# gambaran_rev1.net
KiCad netlist of a schematic drawn in EAGLE
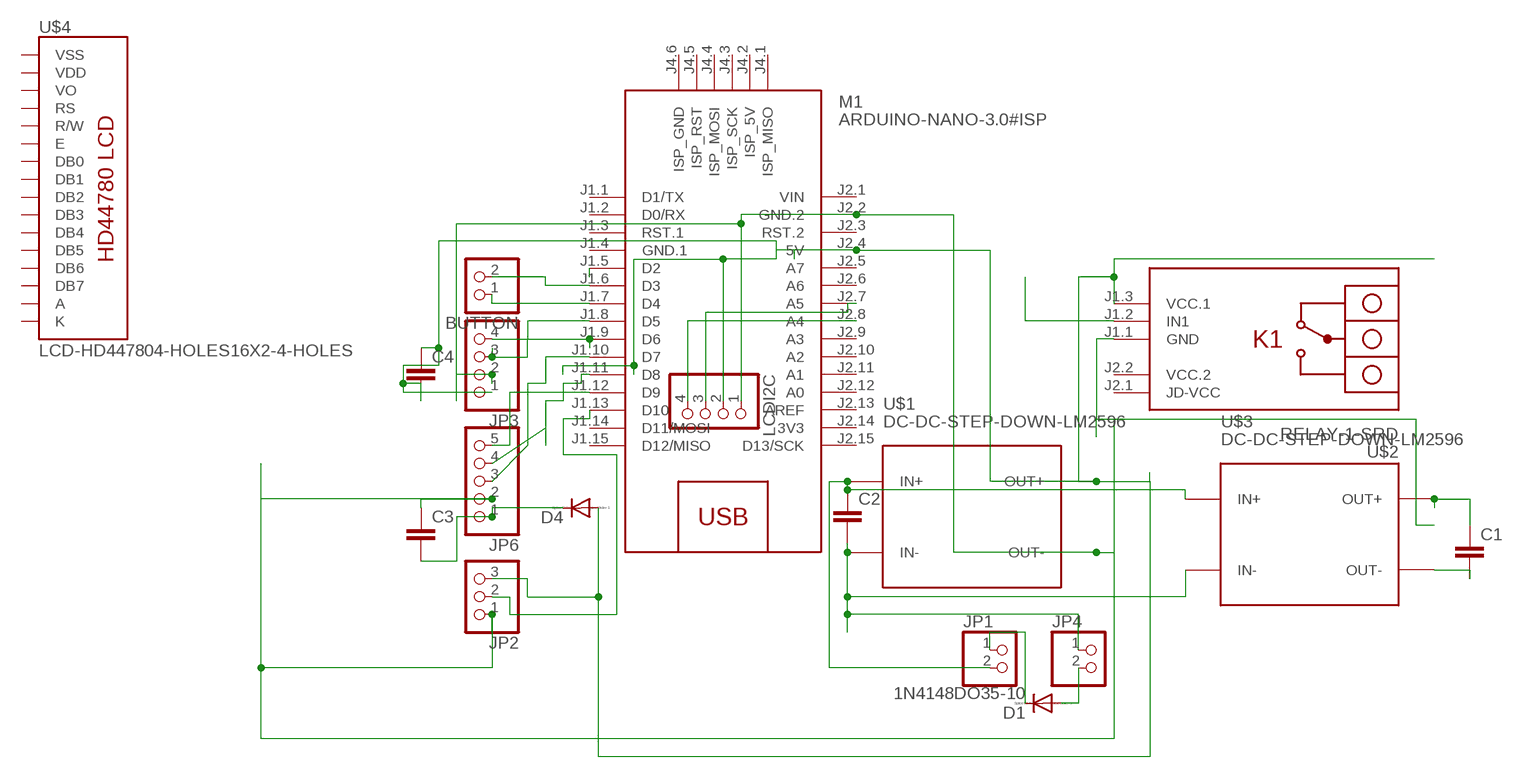
[diagram p0: schematic, sheet 1]

(export (version "E")
  (design (tool "Eeschema 10.0.6"))
  (components
    (comp (ref "BUTTON")
      (value "PINHD-1X2/90")
      (footprint "eagle-import:1X02_90")
      (libsource (lib "eagle-import") (part "PINHD-1X2/90"))
    )
    (comp (ref "C1")
      (value "C2.5/6")
      (footprint "eagle-import:C2.5-6")
      (libsource (lib "eagle-import") (part "C2.5/6"))
    )
    (comp (ref "C2")
      (value "C2.5/6")
      (footprint "eagle-import:C2.5-6")
      (libsource (lib "eagle-import") (part "C2.5/6"))
    )
    (comp (ref "C3")
      (value "C2.5/6")
      (footprint "eagle-import:C2.5-6")
      (libsource (lib "eagle-import") (part "C2.5/6"))
    )
    (comp (ref "C4")
      (value "C2.5/6")
      (footprint "eagle-import:C2.5-6")
      (libsource (lib "eagle-import") (part "C2.5/6"))
    )
    (comp (ref "D1")
      (value "1N4148DO35-10")
      (footprint "eagle-import:DO35-10")
      (libsource (lib "eagle-import") (part "1N4148DO35-10"))
    )
    (comp (ref "D4")
      (value "1N4148DO35-10")
      (footprint "eagle-import:DO35-10")
      (libsource (lib "eagle-import") (part "1N4148DO35-10"))
    )
    (comp (ref "JP1")
      (value "PINHD-1X2/90")
      (footprint "eagle-import:1X02_90")
      (libsource (lib "eagle-import") (part "PINHD-1X2/90"))
    )
    (comp (ref "JP2")
      (value "PINHD-1X3")
      (footprint "eagle-import:1X03")
      (libsource (lib "eagle-import") (part "PINHD-1X3"))
    )
    (comp (ref "JP3")
      (value "PINHD-1X4/90")
      (footprint "eagle-import:1X04_90")
      (libsource (lib "eagle-import") (part "PINHD-1X4/90"))
    )
    (comp (ref "JP4")
      (value "PINHD-1X2/90")
      (footprint "eagle-import:1X02_90")
      (libsource (lib "eagle-import") (part "PINHD-1X2/90"))
    )
    (comp (ref "JP6")
      (value "PINHD-1X5")
      (footprint "eagle-import:1X05")
      (libsource (lib "eagle-import") (part "PINHD-1X5"))
    )
    (comp (ref "LCDI2C")
      (value "PINHD-1X4/90")
      (footprint "eagle-import:1X04_90")
      (libsource (lib "eagle-import") (part "PINHD-1X4/90"))
    )
    (comp (ref "M1")
      (value "ARDUINO-NANO-3.0#ISP")
      (footprint "eagle-import:ARDUINO-NANO-3.0#ISP")
      (libsource (lib "eagle-import") (part "ARDUINO-NANO-3.0#ISP"))
    )
    (comp (ref "U$1")
      (value "DC-DC-STEP-DOWN-LM2596")
      (footprint "eagle-import:DC-DC-STEP-DOWN-LM2596")
      (libsource (lib "eagle-import") (part "DC-DC-STEP-DOWN-LM2596"))
    )
    (comp (ref "U$2")
      (value "RELAY-1-SRD")
      (footprint "eagle-import:RELAY-1-SRD")
      (libsource (lib "eagle-import") (part "RELAY-1-SRD"))
    )
    (comp (ref "U$3")
      (value "DC-DC-STEP-DOWN-LM2596")
      (footprint "eagle-import:DC-DC-STEP-DOWN-LM2596")
      (libsource (lib "eagle-import") (part "DC-DC-STEP-DOWN-LM2596"))
    )
    (comp (ref "U$4")
      (value "LCD-HD447804-HOLES16X2-4-HOLES")
      (footprint "eagle-import:LCD-16X2-4HOLES")
      (libsource (lib "eagle-import") (part "LCD-HD4478016X2-4-HOLES4-HOLES"))
    )
  )
  (nets
    (net (code "1") (name "/3V3") (class "Default")
      (node (ref "M1") (pin "J2.14") (pinfunction "3V3_J2.14") (pintype "power_in"))
    )
    (net (code "2") (name "/A") (class "Default")
      (node (ref "U$4") (pin "15") (pinfunction "A_15") (pintype "power_in"))
    )
    (net (code "3") (name "/GND.1") (class "Default")
      (node (ref "M1") (pin "J1.4") (pinfunction "GND.1_J1.4") (pintype "power_in"))
    )
    (net (code "4") (name "/K") (class "Default")
      (node (ref "U$4") (pin "16") (pinfunction "K_16") (pintype "power_in"))
    )
    (net (code "5") (name "/VCC.2") (class "Default")
      (node (ref "U$2") (pin "J2.2") (pinfunction "VCC.2_J2.2") (pintype "power_in"))
    )
    (net (code "6") (name "/VDD") (class "Default")
      (node (ref "U$4") (pin "2") (pinfunction "VDD_2") (pintype "power_in"))
    )
    (net (code "7") (name "/VIN") (class "Default")
      (node (ref "M1") (pin "J2.1") (pinfunction "VIN_J2.1") (pintype "power_in"))
    )
    (net (code "8") (name "/VSS") (class "Default")
      (node (ref "U$4") (pin "1") (pinfunction "VSS_1") (pintype "power_in"))
    )
    (net (code "9") (name "Net-(C1-Pad1)") (class "Default")
      (node (ref "C1") (pin "1") (pinfunction "1_1") (pintype "passive"))
      (node (ref "U$3") (pin "OUT+") (pinfunction "OUT+_OUT+") (pintype "bidirectional"))
    )
    (net (code "10") (name "Net-(C1-Pad2)") (class "Default")
      (node (ref "C1") (pin "2") (pinfunction "2_2") (pintype "passive"))
      (node (ref "U$3") (pin "OUT-") (pinfunction "OUT-_OUT-") (pintype "bidirectional"))
    )
    (net (code "11") (name "Net-(C2-Pad1)") (class "Default")
      (node (ref "C2") (pin "1") (pinfunction "1_1") (pintype "passive"))
      (node (ref "JP1") (pin "2") (pinfunction "2_2") (pintype "passive"))
      (node (ref "U$1") (pin "IN+") (pinfunction "IN+_IN+") (pintype "bidirectional"))
      (node (ref "U$3") (pin "IN+") (pinfunction "IN+_IN+") (pintype "bidirectional"))
    )
    (net (code "12") (name "Net-(C2-Pad2)") (class "Default")
      (node (ref "C2") (pin "2") (pinfunction "2_2") (pintype "passive"))
      (node (ref "JP4") (pin "1") (pinfunction "1_1") (pintype "passive"))
      (node (ref "U$1") (pin "IN-") (pinfunction "IN-_IN-") (pintype "bidirectional"))
      (node (ref "U$3") (pin "IN-") (pinfunction "IN-_IN-") (pintype "bidirectional"))
    )
    (net (code "13") (name "Net-(C3-Pad2)") (class "Default")
      (node (ref "C3") (pin "2") (pinfunction "2_2") (pintype "passive"))
      (node (ref "D4") (pin "C") (pinfunction "C_C") (pintype "passive"))
      (node (ref "JP6") (pin "1") (pinfunction "1_1") (pintype "passive"))
    )
    (net (code "14") (name "Net-(D1-PadA)") (class "Default")
      (node (ref "D1") (pin "A") (pinfunction "A_A") (pintype "passive"))
      (node (ref "JP4") (pin "2") (pinfunction "2_2") (pintype "passive"))
    )
    (net (code "15") (name "Net-(D1-PadC)") (class "Default")
      (node (ref "D1") (pin "C") (pinfunction "C_C") (pintype "passive"))
      (node (ref "JP1") (pin "1") (pinfunction "1_1") (pintype "passive"))
    )
    (net (code "16") (name "Net-(M1-5V)") (class "Default")
      (node (ref "C4") (pin "1") (pinfunction "1_1") (pintype "passive"))
      (node (ref "C4") (pin "2") (pinfunction "2_2") (pintype "passive"))
      (node (ref "D4") (pin "A") (pinfunction "A_A") (pintype "passive"))
      (node (ref "JP2") (pin "3") (pinfunction "3_3") (pintype "passive"))
      (node (ref "JP3") (pin "1") (pinfunction "1_1") (pintype "passive"))
      (node (ref "LCDI2C") (pin "2") (pinfunction "2_2") (pintype "passive"))
      (node (ref "M1") (pin "J2.4") (pinfunction "5V_J2.4") (pintype "power_in"))
      (node (ref "U$1") (pin "OUT+") (pinfunction "OUT+_OUT+") (pintype "bidirectional"))
      (node (ref "U$2") (pin "J1.3") (pinfunction "VCC.1_J1.3") (pintype "power_in"))
    )
    (net (code "17") (name "Net-(M1-A4)") (class "Default")
      (node (ref "LCDI2C") (pin "4") (pinfunction "4_4") (pintype "passive"))
      (node (ref "M1") (pin "J2.8") (pinfunction "A4_J2.8") (pintype "bidirectional"))
    )
    (net (code "18") (name "Net-(M1-A5)") (class "Default")
      (node (ref "LCDI2C") (pin "3") (pinfunction "3_3") (pintype "passive"))
      (node (ref "M1") (pin "J2.7") (pinfunction "A5_J2.7") (pintype "bidirectional"))
    )
    (net (code "19") (name "Net-(M1-D3)") (class "Default")
      (node (ref "BUTTON") (pin "2") (pinfunction "2_2") (pintype "passive"))
      (node (ref "M1") (pin "J1.6") (pinfunction "D3_J1.6") (pintype "bidirectional"))
    )
    (net (code "20") (name "Net-(M1-D4)") (class "Default")
      (node (ref "BUTTON") (pin "1") (pinfunction "1_1") (pintype "passive"))
      (node (ref "M1") (pin "J1.7") (pinfunction "D4_J1.7") (pintype "bidirectional"))
    )
    (net (code "21") (name "Net-(M1-D5)") (class "Default")
      (node (ref "JP3") (pin "3") (pinfunction "3_3") (pintype "passive"))
      (node (ref "M1") (pin "J1.8") (pinfunction "D5_J1.8") (pintype "bidirectional"))
    )
    (net (code "22") (name "Net-(M1-D6)") (class "Default")
      (node (ref "JP3") (pin "4") (pinfunction "4_4") (pintype "passive"))
      (node (ref "M1") (pin "J1.9") (pinfunction "D6_J1.9") (pintype "bidirectional"))
    )
    (net (code "23") (name "Net-(M1-D7)") (class "Default")
      (node (ref "JP6") (pin "3") (pinfunction "3_3") (pintype "passive"))
      (node (ref "M1") (pin "J1.10") (pinfunction "D7_J1.10") (pintype "bidirectional"))
    )
    (net (code "24") (name "Net-(M1-D8)") (class "Default")
      (node (ref "JP6") (pin "4") (pinfunction "4_4") (pintype "passive"))
      (node (ref "M1") (pin "J1.11") (pinfunction "D8_J1.11") (pintype "bidirectional"))
    )
    (net (code "25") (name "Net-(M1-D9)") (class "Default")
      (node (ref "JP6") (pin "5") (pinfunction "5_5") (pintype "passive"))
      (node (ref "M1") (pin "J1.12") (pinfunction "D9_J1.12") (pintype "bidirectional"))
    )
    (net (code "26") (name "Net-(M1-D10)") (class "Default")
      (node (ref "JP2") (pin "2") (pinfunction "2_2") (pintype "passive"))
      (node (ref "M1") (pin "J1.13") (pinfunction "D10_J1.13") (pintype "bidirectional"))
    )
    (net (code "27") (name "Net-(M1-GND.2)") (class "Default")
      (node (ref "C3") (pin "1") (pinfunction "1_1") (pintype "passive"))
      (node (ref "JP2") (pin "1") (pinfunction "1_1") (pintype "passive"))
      (node (ref "JP3") (pin "2") (pinfunction "2_2") (pintype "passive"))
      (node (ref "JP6") (pin "2") (pinfunction "2_2") (pintype "passive"))
      (node (ref "LCDI2C") (pin "1") (pinfunction "1_1") (pintype "passive"))
      (node (ref "M1") (pin "J2.2") (pinfunction "GND.2_J2.2") (pintype "power_in"))
      (node (ref "U$1") (pin "OUT-") (pinfunction "OUT-_OUT-") (pintype "bidirectional"))
      (node (ref "U$2") (pin "J1.1") (pinfunction "GND_J1.1") (pintype "power_in"))
    )
    (net (code "28") (name "unconnected-(M1-A0-PadJ2.12)") (class "Default")
      (node (ref "M1") (pin "J2.12") (pinfunction "A0_J2.12") (pintype "bidirectional"))
    )
    (net (code "29") (name "unconnected-(M1-A1-PadJ2.11)") (class "Default")
      (node (ref "M1") (pin "J2.11") (pinfunction "A1_J2.11") (pintype "bidirectional"))
    )
    (net (code "30") (name "unconnected-(M1-A2-PadJ2.10)") (class "Default")
      (node (ref "M1") (pin "J2.10") (pinfunction "A2_J2.10") (pintype "bidirectional"))
    )
    (net (code "31") (name "unconnected-(M1-A3-PadJ2.9)") (class "Default")
      (node (ref "M1") (pin "J2.9") (pinfunction "A3_J2.9") (pintype "bidirectional"))
    )
    (net (code "32") (name "unconnected-(M1-A6-PadJ2.6)") (class "Default")
      (node (ref "M1") (pin "J2.6") (pinfunction "A6_J2.6") (pintype "bidirectional"))
    )
    (net (code "33") (name "unconnected-(M1-A7-PadJ2.5)") (class "Default")
      (node (ref "M1") (pin "J2.5") (pinfunction "A7_J2.5") (pintype "bidirectional"))
    )
    (net (code "34") (name "unconnected-(M1-AREF-PadJ2.13)") (class "Default")
      (node (ref "M1") (pin "J2.13") (pinfunction "AREF_J2.13") (pintype "bidirectional"))
    )
    (net (code "35") (name "unconnected-(M1-D0{slash}RX-PadJ1.2)") (class "Default")
      (node (ref "M1") (pin "J1.2") (pinfunction "D0/RX_J1.2") (pintype "bidirectional"))
    )
    (net (code "36") (name "unconnected-(M1-D1{slash}TX-PadJ1.1)") (class "Default")
      (node (ref "M1") (pin "J1.1") (pinfunction "D1/TX_J1.1") (pintype "bidirectional"))
    )
    (net (code "37") (name "unconnected-(M1-D2-PadJ1.5)") (class "Default")
      (node (ref "M1") (pin "J1.5") (pinfunction "D2_J1.5") (pintype "bidirectional"))
    )
    (net (code "38") (name "unconnected-(M1-D11{slash}MOSI-PadJ1.14)") (class "Default")
      (node (ref "M1") (pin "J1.14") (pinfunction "D11/MOSI_J1.14") (pintype "bidirectional"))
    )
    (net (code "39") (name "unconnected-(M1-D12{slash}MISO-PadJ1.15)") (class "Default")
      (node (ref "M1") (pin "J1.15") (pinfunction "D12/MISO_J1.15") (pintype "bidirectional"))
    )
    (net (code "40") (name "unconnected-(M1-D13{slash}SCK-PadJ2.15)") (class "Default")
      (node (ref "M1") (pin "J2.15") (pinfunction "D13/SCK_J2.15") (pintype "bidirectional"))
    )
    (net (code "41") (name "unconnected-(M1-ISP_5V-PadJ4.2)") (class "Default")
      (node (ref "M1") (pin "J4.2") (pinfunction "ISP_5V_J4.2") (pintype "bidirectional"))
    )
    (net (code "42") (name "unconnected-(M1-ISP_GND-PadJ4.6)") (class "Default")
      (node (ref "M1") (pin "J4.6") (pinfunction "ISP_GND_J4.6") (pintype "bidirectional"))
    )
    (net (code "43") (name "unconnected-(M1-ISP_MISO-PadJ4.1)") (class "Default")
      (node (ref "M1") (pin "J4.1") (pinfunction "ISP_MISO_J4.1") (pintype "bidirectional"))
    )
    (net (code "44") (name "unconnected-(M1-ISP_MOSI-PadJ4.4)") (class "Default")
      (node (ref "M1") (pin "J4.4") (pinfunction "ISP_MOSI_J4.4") (pintype "bidirectional"))
    )
    (net (code "45") (name "unconnected-(M1-ISP_RST-PadJ4.5)") (class "Default")
      (node (ref "M1") (pin "J4.5") (pinfunction "ISP_RST_J4.5") (pintype "bidirectional"))
    )
    (net (code "46") (name "unconnected-(M1-ISP_SCK-PadJ4.3)") (class "Default")
      (node (ref "M1") (pin "J4.3") (pinfunction "ISP_SCK_J4.3") (pintype "bidirectional"))
    )
    (net (code "47") (name "unconnected-(M1-RST.1-PadJ1.3)") (class "Default")
      (node (ref "M1") (pin "J1.3") (pinfunction "RST.1_J1.3") (pintype "bidirectional"))
    )
    (net (code "48") (name "unconnected-(M1-RST.2-PadJ2.3)") (class "Default")
      (node (ref "M1") (pin "J2.3") (pinfunction "RST.2_J2.3") (pintype "bidirectional"))
    )
    (net (code "49") (name "unconnected-(U$2-IN1-PadJ1.2)") (class "Default")
      (node (ref "U$2") (pin "J1.2") (pinfunction "IN1_J1.2") (pintype "bidirectional"))
    )
    (net (code "50") (name "unconnected-(U$2-JD-VCC-PadJ2.1)") (class "Default")
      (node (ref "U$2") (pin "J2.1") (pinfunction "JD-VCC_J2.1") (pintype "bidirectional"))
    )
    (net (code "51") (name "unconnected-(U$4-DB0-Pad7)") (class "Default")
      (node (ref "U$4") (pin "7") (pinfunction "DB0_7") (pintype "bidirectional"))
    )
    (net (code "52") (name "unconnected-(U$4-DB1-Pad8)") (class "Default")
      (node (ref "U$4") (pin "8") (pinfunction "DB1_8") (pintype "bidirectional"))
    )
    (net (code "53") (name "unconnected-(U$4-DB2-Pad9)") (class "Default")
      (node (ref "U$4") (pin "9") (pinfunction "DB2_9") (pintype "bidirectional"))
    )
    (net (code "54") (name "unconnected-(U$4-DB3-Pad10)") (class "Default")
      (node (ref "U$4") (pin "10") (pinfunction "DB3_10") (pintype "bidirectional"))
    )
    (net (code "55") (name "unconnected-(U$4-DB4-Pad11)") (class "Default")
      (node (ref "U$4") (pin "11") (pinfunction "DB4_11") (pintype "bidirectional"))
    )
    (net (code "56") (name "unconnected-(U$4-DB5-Pad12)") (class "Default")
      (node (ref "U$4") (pin "12") (pinfunction "DB5_12") (pintype "bidirectional"))
    )
    (net (code "57") (name "unconnected-(U$4-DB6-Pad13)") (class "Default")
      (node (ref "U$4") (pin "13") (pinfunction "DB6_13") (pintype "bidirectional"))
    )
    (net (code "58") (name "unconnected-(U$4-DB7-Pad14)") (class "Default")
      (node (ref "U$4") (pin "14") (pinfunction "DB7_14") (pintype "bidirectional"))
    )
    (net (code "59") (name "unconnected-(U$4-E-Pad6)") (class "Default")
      (node (ref "U$4") (pin "6") (pinfunction "E_6") (pintype "input"))
    )
    (net (code "60") (name "unconnected-(U$4-RS-Pad4)") (class "Default")
      (node (ref "U$4") (pin "4") (pinfunction "RS_4") (pintype "input"))
    )
    (net (code "61") (name "unconnected-(U$4-R{slash}W-Pad5)") (class "Default")
      (node (ref "U$4") (pin "5") (pinfunction "R/W_5") (pintype "input"))
    )
    (net (code "62") (name "unconnected-(U$4-VO-Pad3)") (class "Default")
      (node (ref "U$4") (pin "3") (pinfunction "VO_3") (pintype "bidirectional"))
    )
  )
)
